# Module24Switches_TH_2025.net
KiCad netlist of a schematic drawn in EasyEDA Pro
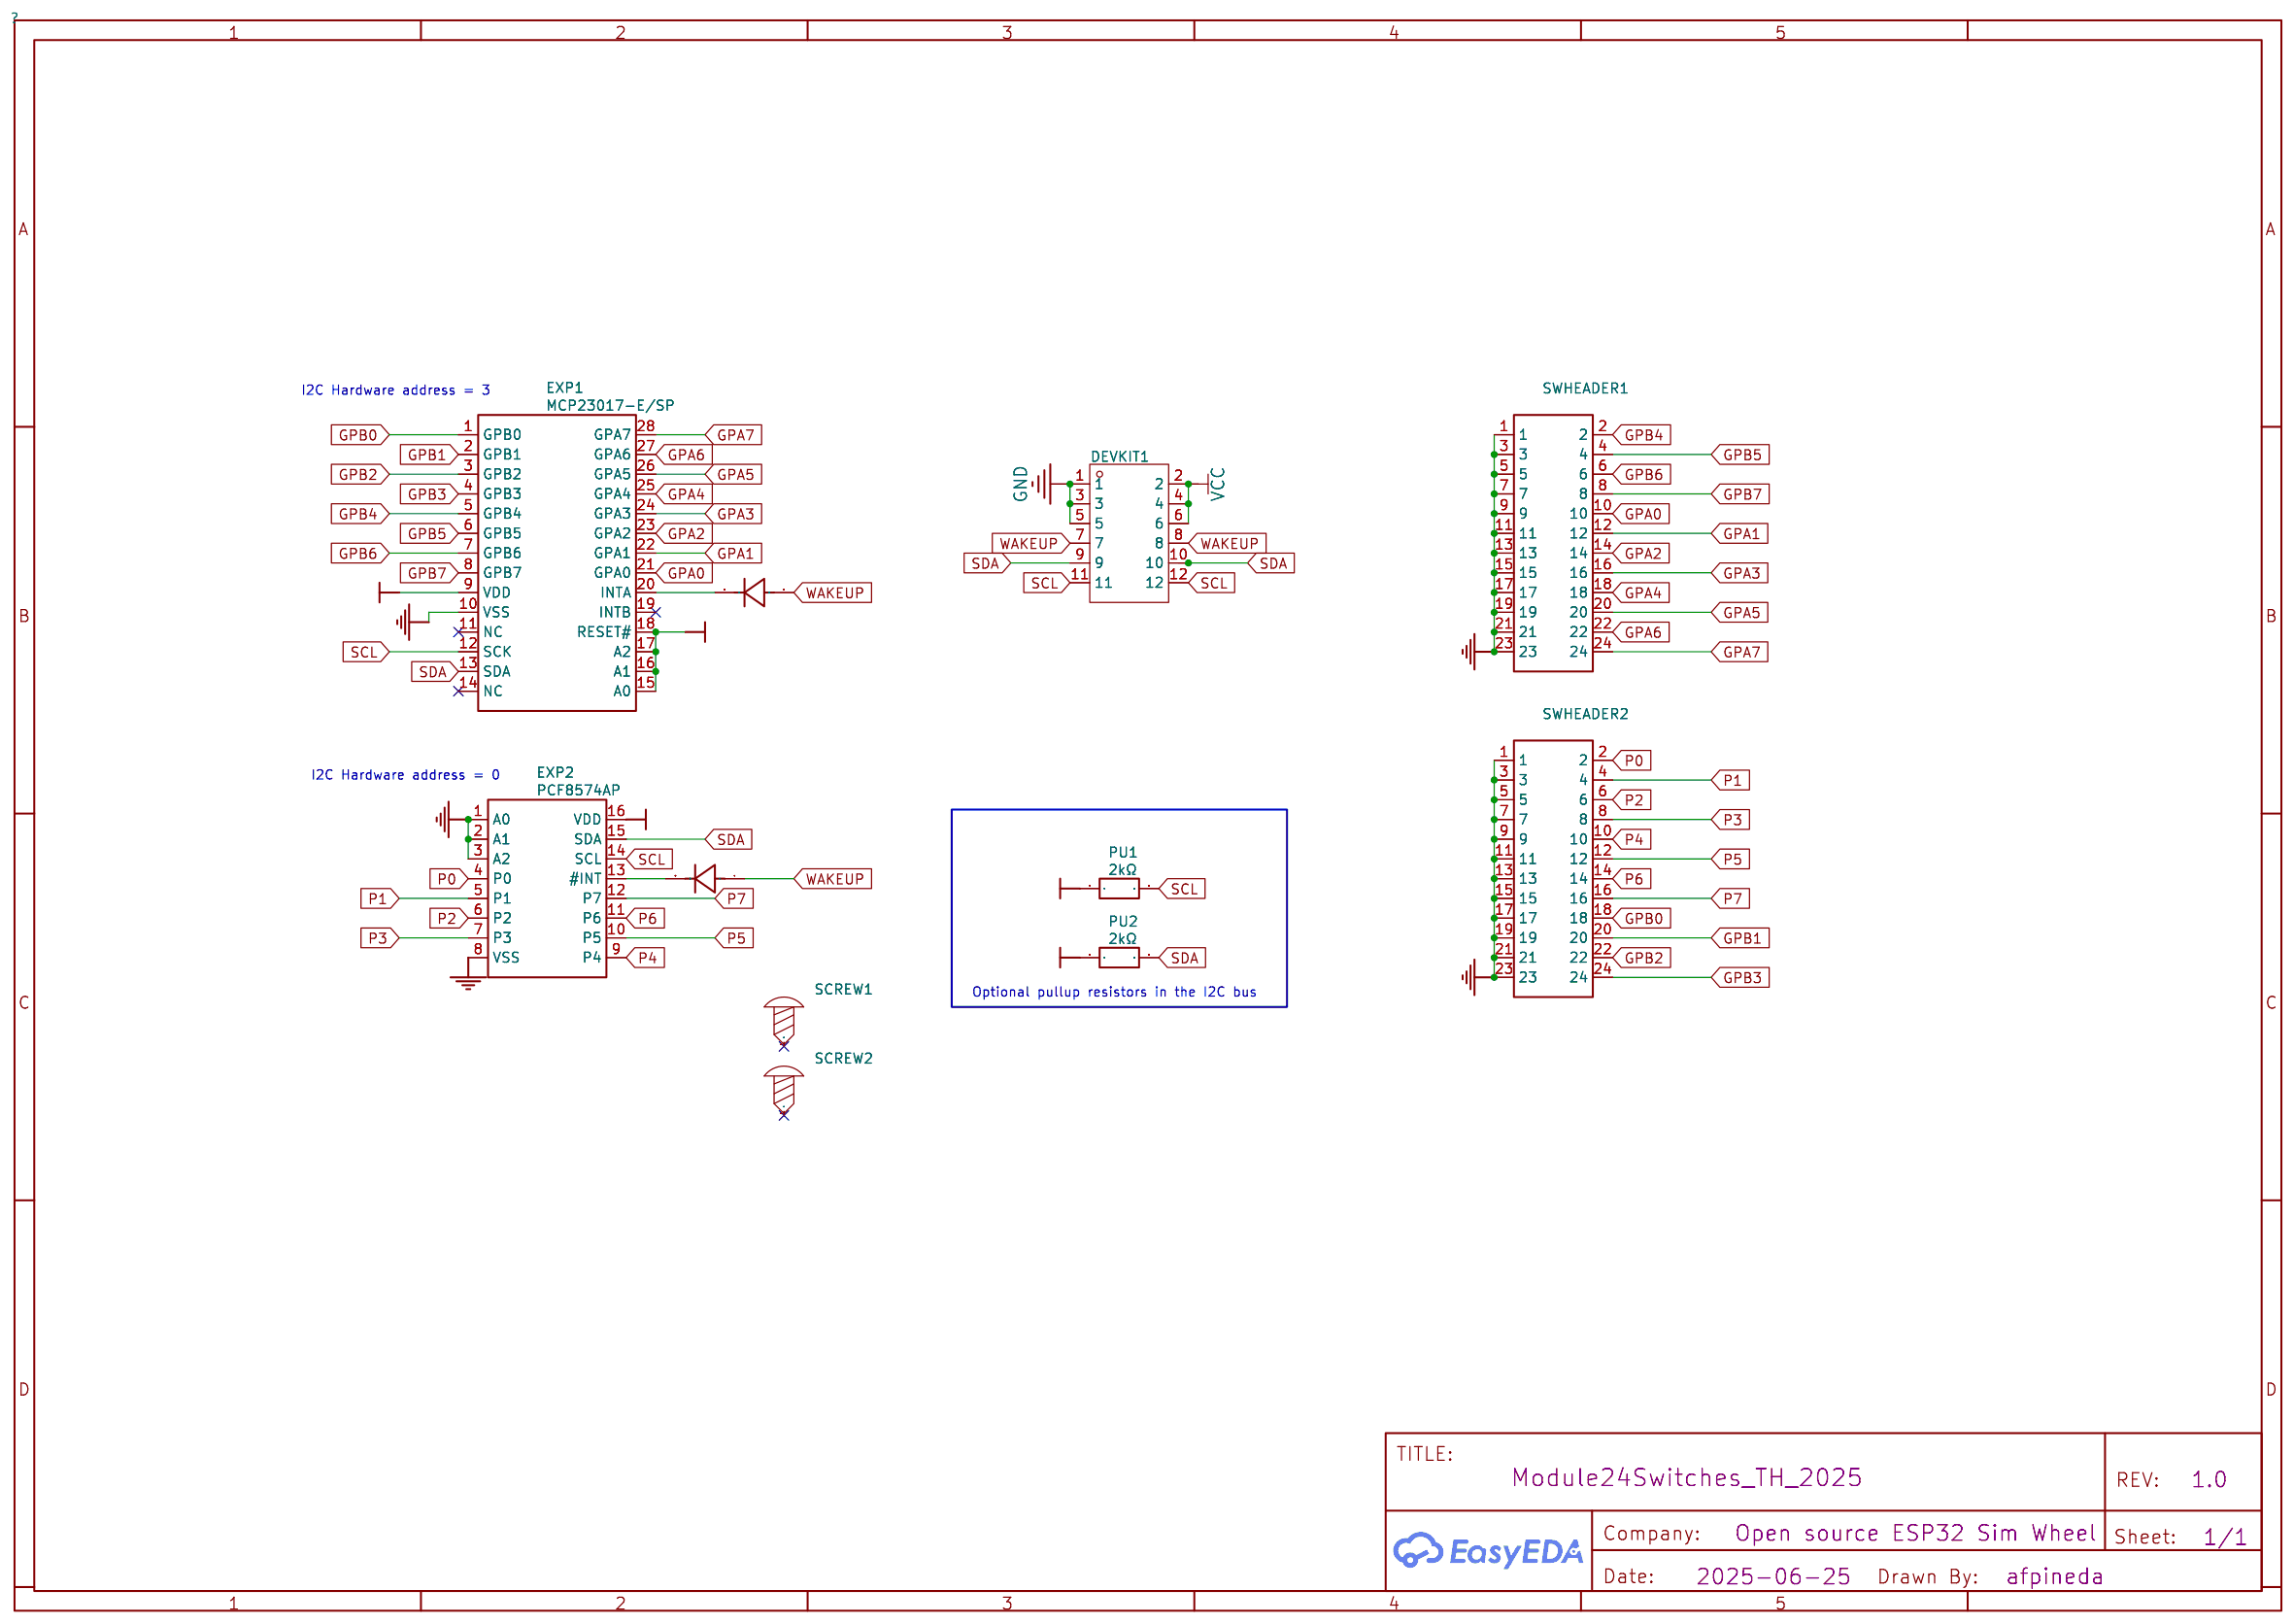
[diagram p0: schematic sheet]

(export (version "E")
  (design (tool "Eeschema 10.0.6"))
  (components
    (comp (ref "D1")
      (value "1N4148_C18195411")
      (footprint "easyedapro:DO-35_BD2.2-L4.0-D0.50_1N4148")
      (fields
        (field (name "Manufacturer Part") "1N4148")
        (field (name "Manufacturer") "LJ(朗捷)")
        (field (name "Contributor") "lcsc")
      )
      (libsource (lib "easyedapro") (part "1N4148_C18195411"))
    )
    (comp (ref "D2")
      (value "1N4148_C18195411")
      (footprint "easyedapro:DO-35_BD2.2-L4.0-D0.50_1N4148")
      (fields
        (field (name "Manufacturer Part") "1N4148")
        (field (name "Manufacturer") "LJ(朗捷)")
        (field (name "Contributor") "lcsc")
      )
      (libsource (lib "easyedapro") (part "1N4148_C18195411"))
    )
    (comp (ref "DEVKIT1")
      (value "2541WR-2x06P")
      (footprint "easyedapro:HDR-TH_12P-P2.54-H-M-R2-C6-S2.54-N")
      (fields (field (name "Manufacturer") "HanElectricity(瀚源)"))
      (libsource (lib "easyedapro") (part "2541WR-2X06P"))
    )
    (comp (ref "EXP1")
      (value "MCP23017-E/SP")
      (footprint "easyedapro:DIP-28_L34.6-W7.3-P2.54-LS10.2-BL")
      (fields (field (name "Manufacturer") "MICROCHIP(美国微芯)") (field (name "Contributor") "LCSC"))
      (libsource (lib "easyedapro") (part "MCP23017-E/SP"))
    )
    (comp (ref "EXP2")
      (value "PCF8574AP")
      (footprint "easyedapro:DIP-16_L19.2-W6.6-P2.54-LS7.6-BL")
      (fields (field (name "Manufacturer") "HGSEMI(华冠)") (field (name "Contributor") "LCSC"))
      (libsource (lib "easyedapro") (part "PCF8574AP"))
    )
    (comp (ref "PU1")
      (value "2kΩ")
      (footprint "easyedapro:RES-TH_BD2.5-L6.5-P10.50-D0.6")
      (fields
        (field (name "Manufacturer Part") "MBB02070C1002FCT00")
        (field (name "Manufacturer") "VISHAY(威世)")
      )
      (libsource (lib "easyedapro") (part "10kΩ"))
    )
    (comp (ref "PU2")
      (value "2kΩ")
      (footprint "easyedapro:RES-TH_BD2.5-L6.5-P10.50-D0.6")
      (fields
        (field (name "Manufacturer Part") "MBB02070C1002FCT00")
        (field (name "Manufacturer") "VISHAY(威世)")
      )
      (libsource (lib "easyedapro") (part "10kΩ"))
    )
    (comp (ref "SCREW1")
      (value "~")
      (footprint "easyedapro:Screw-Hole-M2")
      (libsource (lib "easyedapro") (part "Screw-Hole"))
    )
    (comp (ref "SCREW2")
      (value "~")
      (footprint "easyedapro:Screw-Hole-M2")
      (libsource (lib "easyedapro") (part "Screw-Hole"))
    )
    (comp (ref "SWHEADER1")
      (value "2541WR-2x12P")
      (footprint "easyedapro:HDR-TH_24P-P2.54-H-M-R2-C12-S2.54-N")
      (fields (field (name "Manufacturer") "HanElectricity(瀚源)"))
      (libsource (lib "easyedapro") (part "2541WR-2X12P"))
    )
    (comp (ref "SWHEADER2")
      (value "2541WR-2x12P")
      (footprint "easyedapro:HDR-TH_24P-P2.54-H-M-R2-C12-S2.54-N")
      (fields (field (name "Manufacturer") "HanElectricity(瀚源)"))
      (libsource (lib "easyedapro") (part "2541WR-2X12P"))
    )
  )
  (nets
    (net (code "1") (name "GND") (class "Default")
      (node (ref "DEVKIT1") (pin "1") (pinfunction "1_1") (pintype "unspecified"))
      (node (ref "DEVKIT1") (pin "3") (pinfunction "3_3") (pintype "unspecified"))
      (node (ref "DEVKIT1") (pin "5") (pinfunction "5_5") (pintype "unspecified"))
      (node (ref "EXP1") (pin "10") (pinfunction "VSS_10") (pintype "unspecified"))
      (node (ref "EXP2") (pin "1") (pinfunction "A0_1") (pintype "unspecified"))
      (node (ref "EXP2") (pin "2") (pinfunction "A1_2") (pintype "unspecified"))
      (node (ref "EXP2") (pin "3") (pinfunction "A2_3") (pintype "unspecified"))
      (node (ref "EXP2") (pin "8") (pinfunction "VSS_8") (pintype "unspecified"))
      (node (ref "SWHEADER1") (pin "1") (pinfunction "1_1") (pintype "unspecified"))
      (node (ref "SWHEADER1") (pin "11") (pinfunction "11_11") (pintype "unspecified"))
      (node (ref "SWHEADER1") (pin "13") (pinfunction "13_13") (pintype "unspecified"))
      (node (ref "SWHEADER1") (pin "15") (pinfunction "15_15") (pintype "unspecified"))
      (node (ref "SWHEADER1") (pin "17") (pinfunction "17_17") (pintype "unspecified"))
      (node (ref "SWHEADER1") (pin "19") (pinfunction "19_19") (pintype "unspecified"))
      (node (ref "SWHEADER1") (pin "21") (pinfunction "21_21") (pintype "unspecified"))
      (node (ref "SWHEADER1") (pin "23") (pinfunction "23_23") (pintype "unspecified"))
      (node (ref "SWHEADER1") (pin "3") (pinfunction "3_3") (pintype "unspecified"))
      (node (ref "SWHEADER1") (pin "5") (pinfunction "5_5") (pintype "unspecified"))
      (node (ref "SWHEADER1") (pin "7") (pinfunction "7_7") (pintype "unspecified"))
      (node (ref "SWHEADER1") (pin "9") (pinfunction "9_9") (pintype "unspecified"))
      (node (ref "SWHEADER2") (pin "1") (pinfunction "1_1") (pintype "unspecified"))
      (node (ref "SWHEADER2") (pin "11") (pinfunction "11_11") (pintype "unspecified"))
      (node (ref "SWHEADER2") (pin "13") (pinfunction "13_13") (pintype "unspecified"))
      (node (ref "SWHEADER2") (pin "15") (pinfunction "15_15") (pintype "unspecified"))
      (node (ref "SWHEADER2") (pin "17") (pinfunction "17_17") (pintype "unspecified"))
      (node (ref "SWHEADER2") (pin "19") (pinfunction "19_19") (pintype "unspecified"))
      (node (ref "SWHEADER2") (pin "21") (pinfunction "21_21") (pintype "unspecified"))
      (node (ref "SWHEADER2") (pin "23") (pinfunction "23_23") (pintype "unspecified"))
      (node (ref "SWHEADER2") (pin "3") (pinfunction "3_3") (pintype "unspecified"))
      (node (ref "SWHEADER2") (pin "5") (pinfunction "5_5") (pintype "unspecified"))
      (node (ref "SWHEADER2") (pin "7") (pinfunction "7_7") (pintype "unspecified"))
      (node (ref "SWHEADER2") (pin "9") (pinfunction "9_9") (pintype "unspecified"))
    )
    (net (code "2") (name "GPA0") (class "Default")
      (node (ref "EXP1") (pin "21") (pinfunction "GPA0_21") (pintype "unspecified"))
      (node (ref "SWHEADER1") (pin "10") (pinfunction "10_10") (pintype "unspecified"))
    )
    (net (code "3") (name "GPA1") (class "Default")
      (node (ref "EXP1") (pin "22") (pinfunction "GPA1_22") (pintype "unspecified"))
      (node (ref "SWHEADER1") (pin "12") (pinfunction "12_12") (pintype "unspecified"))
    )
    (net (code "4") (name "GPA2") (class "Default")
      (node (ref "EXP1") (pin "23") (pinfunction "GPA2_23") (pintype "unspecified"))
      (node (ref "SWHEADER1") (pin "14") (pinfunction "14_14") (pintype "unspecified"))
    )
    (net (code "5") (name "GPA3") (class "Default")
      (node (ref "EXP1") (pin "24") (pinfunction "GPA3_24") (pintype "unspecified"))
      (node (ref "SWHEADER1") (pin "16") (pinfunction "16_16") (pintype "unspecified"))
    )
    (net (code "6") (name "GPA4") (class "Default")
      (node (ref "EXP1") (pin "25") (pinfunction "GPA4_25") (pintype "unspecified"))
      (node (ref "SWHEADER1") (pin "18") (pinfunction "18_18") (pintype "unspecified"))
    )
    (net (code "7") (name "GPA5") (class "Default")
      (node (ref "EXP1") (pin "26") (pinfunction "GPA5_26") (pintype "unspecified"))
      (node (ref "SWHEADER1") (pin "20") (pinfunction "20_20") (pintype "unspecified"))
    )
    (net (code "8") (name "GPA6") (class "Default")
      (node (ref "EXP1") (pin "27") (pinfunction "GPA6_27") (pintype "unspecified"))
      (node (ref "SWHEADER1") (pin "22") (pinfunction "22_22") (pintype "unspecified"))
    )
    (net (code "9") (name "GPA7") (class "Default")
      (node (ref "EXP1") (pin "28") (pinfunction "GPA7_28") (pintype "unspecified"))
      (node (ref "SWHEADER1") (pin "24") (pinfunction "24_24") (pintype "unspecified"))
    )
    (net (code "10") (name "GPB0") (class "Default")
      (node (ref "EXP1") (pin "1") (pinfunction "GPB0_1") (pintype "unspecified"))
      (node (ref "SWHEADER2") (pin "18") (pinfunction "18_18") (pintype "unspecified"))
    )
    (net (code "11") (name "GPB1") (class "Default")
      (node (ref "EXP1") (pin "2") (pinfunction "GPB1_2") (pintype "unspecified"))
      (node (ref "SWHEADER2") (pin "20") (pinfunction "20_20") (pintype "unspecified"))
    )
    (net (code "12") (name "GPB2") (class "Default")
      (node (ref "EXP1") (pin "3") (pinfunction "GPB2_3") (pintype "unspecified"))
      (node (ref "SWHEADER2") (pin "22") (pinfunction "22_22") (pintype "unspecified"))
    )
    (net (code "13") (name "GPB3") (class "Default")
      (node (ref "EXP1") (pin "4") (pinfunction "GPB3_4") (pintype "unspecified"))
      (node (ref "SWHEADER2") (pin "24") (pinfunction "24_24") (pintype "unspecified"))
    )
    (net (code "14") (name "GPB4") (class "Default")
      (node (ref "EXP1") (pin "5") (pinfunction "GPB4_5") (pintype "unspecified"))
      (node (ref "SWHEADER1") (pin "2") (pinfunction "2_2") (pintype "unspecified"))
    )
    (net (code "15") (name "GPB5") (class "Default")
      (node (ref "EXP1") (pin "6") (pinfunction "GPB5_6") (pintype "unspecified"))
      (node (ref "SWHEADER1") (pin "4") (pinfunction "4_4") (pintype "unspecified"))
    )
    (net (code "16") (name "GPB6") (class "Default")
      (node (ref "EXP1") (pin "7") (pinfunction "GPB6_7") (pintype "unspecified"))
      (node (ref "SWHEADER1") (pin "6") (pinfunction "6_6") (pintype "unspecified"))
    )
    (net (code "17") (name "GPB7") (class "Default")
      (node (ref "EXP1") (pin "8") (pinfunction "GPB7_8") (pintype "unspecified"))
      (node (ref "SWHEADER1") (pin "8") (pinfunction "8_8") (pintype "unspecified"))
    )
    (net (code "18") (name "Net-(D1-C)") (class "Default")
      (node (ref "D1") (pin "2") (pinfunction "C_2") (pintype "unspecified"))
      (node (ref "EXP1") (pin "20") (pinfunction "INTA_20") (pintype "unspecified"))
    )
    (net (code "19") (name "Net-(D2-C)") (class "Default")
      (node (ref "D2") (pin "2") (pinfunction "C_2") (pintype "unspecified"))
      (node (ref "EXP2") (pin "13") (pinfunction "#INT_13") (pintype "unspecified"))
    )
    (net (code "20") (name "P0") (class "Default")
      (node (ref "EXP2") (pin "4") (pinfunction "P0_4") (pintype "unspecified"))
      (node (ref "SWHEADER2") (pin "2") (pinfunction "2_2") (pintype "unspecified"))
    )
    (net (code "21") (name "P1") (class "Default")
      (node (ref "EXP2") (pin "5") (pinfunction "P1_5") (pintype "unspecified"))
      (node (ref "SWHEADER2") (pin "4") (pinfunction "4_4") (pintype "unspecified"))
    )
    (net (code "22") (name "P2") (class "Default")
      (node (ref "EXP2") (pin "6") (pinfunction "P2_6") (pintype "unspecified"))
      (node (ref "SWHEADER2") (pin "6") (pinfunction "6_6") (pintype "unspecified"))
    )
    (net (code "23") (name "P3") (class "Default")
      (node (ref "EXP2") (pin "7") (pinfunction "P3_7") (pintype "unspecified"))
      (node (ref "SWHEADER2") (pin "8") (pinfunction "8_8") (pintype "unspecified"))
    )
    (net (code "24") (name "P4") (class "Default")
      (node (ref "EXP2") (pin "9") (pinfunction "P4_9") (pintype "unspecified"))
      (node (ref "SWHEADER2") (pin "10") (pinfunction "10_10") (pintype "unspecified"))
    )
    (net (code "25") (name "P5") (class "Default")
      (node (ref "EXP2") (pin "10") (pinfunction "P5_10") (pintype "unspecified"))
      (node (ref "SWHEADER2") (pin "12") (pinfunction "12_12") (pintype "unspecified"))
    )
    (net (code "26") (name "P6") (class "Default")
      (node (ref "EXP2") (pin "11") (pinfunction "P6_11") (pintype "unspecified"))
      (node (ref "SWHEADER2") (pin "14") (pinfunction "14_14") (pintype "unspecified"))
    )
    (net (code "27") (name "P7") (class "Default")
      (node (ref "EXP2") (pin "12") (pinfunction "P7_12") (pintype "unspecified"))
      (node (ref "SWHEADER2") (pin "16") (pinfunction "16_16") (pintype "unspecified"))
    )
    (net (code "28") (name "SCL") (class "Default")
      (node (ref "DEVKIT1") (pin "11") (pinfunction "11_11") (pintype "unspecified"))
      (node (ref "DEVKIT1") (pin "12") (pinfunction "12_12") (pintype "unspecified"))
      (node (ref "EXP1") (pin "12") (pinfunction "SCK_12") (pintype "unspecified"))
      (node (ref "EXP2") (pin "14") (pinfunction "SCL_14") (pintype "unspecified"))
      (node (ref "PU1") (pin "2") (pinfunction "2_2") (pintype "unspecified"))
    )
    (net (code "29") (name "SDA") (class "Default")
      (node (ref "DEVKIT1") (pin "10") (pinfunction "10_10") (pintype "unspecified"))
      (node (ref "DEVKIT1") (pin "9") (pinfunction "9_9") (pintype "unspecified"))
      (node (ref "EXP1") (pin "13") (pinfunction "SDA_13") (pintype "unspecified"))
      (node (ref "EXP2") (pin "15") (pinfunction "SDA_15") (pintype "unspecified"))
      (node (ref "PU2") (pin "2") (pinfunction "2_2") (pintype "unspecified"))
    )
    (net (code "30") (name "VCC") (class "Default")
      (node (ref "DEVKIT1") (pin "2") (pinfunction "2_2") (pintype "unspecified"))
      (node (ref "DEVKIT1") (pin "4") (pinfunction "4_4") (pintype "unspecified"))
      (node (ref "DEVKIT1") (pin "6") (pinfunction "6_6") (pintype "unspecified"))
      (node (ref "EXP1") (pin "15") (pinfunction "A0_15") (pintype "unspecified"))
      (node (ref "EXP1") (pin "16") (pinfunction "A1_16") (pintype "unspecified"))
      (node (ref "EXP1") (pin "17") (pinfunction "A2_17") (pintype "unspecified"))
      (node (ref "EXP1") (pin "18") (pinfunction "RESET#_18") (pintype "unspecified"))
      (node (ref "EXP1") (pin "9") (pinfunction "VDD_9") (pintype "unspecified"))
      (node (ref "EXP2") (pin "16") (pinfunction "VDD_16") (pintype "unspecified"))
      (node (ref "PU1") (pin "1") (pinfunction "1_1") (pintype "unspecified"))
      (node (ref "PU2") (pin "1") (pinfunction "1_1") (pintype "unspecified"))
    )
    (net (code "31") (name "WAKEUP") (class "Default")
      (node (ref "D1") (pin "1") (pinfunction "A_1") (pintype "unspecified"))
      (node (ref "D2") (pin "1") (pinfunction "A_1") (pintype "unspecified"))
      (node (ref "DEVKIT1") (pin "7") (pinfunction "7_7") (pintype "unspecified"))
      (node (ref "DEVKIT1") (pin "8") (pinfunction "8_8") (pintype "unspecified"))
    )
    (net (code "32") (name "unconnected-(EXP1-INTB-Pad19)") (class "Default")
      (node (ref "EXP1") (pin "19") (pinfunction "INTB_19") (pintype "unspecified+no_connect"))
    )
    (net (code "33") (name "unconnected-(EXP1-NC-Pad11)") (class "Default")
      (node (ref "EXP1") (pin "11") (pinfunction "NC_11") (pintype "unspecified+no_connect"))
    )
    (net (code "34") (name "unconnected-(EXP1-NC-Pad14)") (class "Default")
      (node (ref "EXP1") (pin "14") (pinfunction "NC_14") (pintype "unspecified+no_connect"))
    )
    (net (code "35") (name "unconnected-(SCREW1-Pad1)") (class "Default")
      (node (ref "SCREW1") (pin "1") (pinfunction "1_1") (pintype "input+no_connect"))
    )
    (net (code "36") (name "unconnected-(SCREW2-Pad1)") (class "Default")
      (node (ref "SCREW2") (pin "1") (pinfunction "1_1") (pintype "input+no_connect"))
    )
  )
)
